# SDRAM.net
KiCad netlist of a schematic drawn in Altium Designer
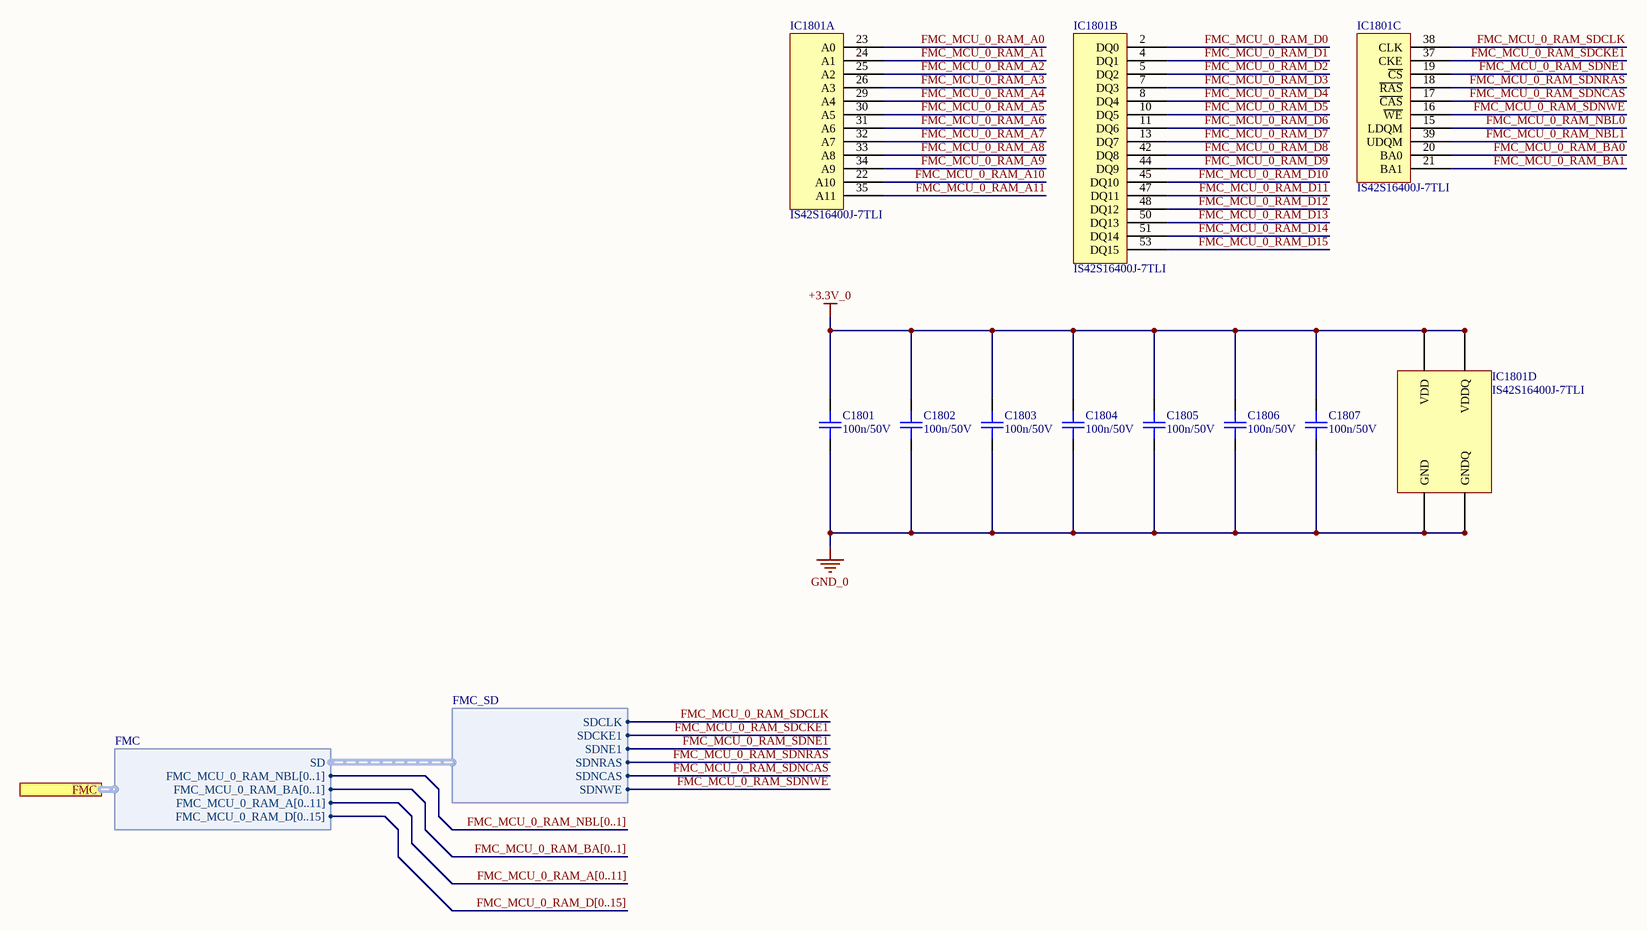
[diagram p0: SDRAM.SchDoc]

(export (version "E")
  (design (tool "Eeschema 10.0.6"))
  (components
    (comp (ref "C1801")
      (value "100n/50V")
      (footprint "CAPC1608X08N")
      (description "MLCC")
      (fields (field (name "PART NUMBER") "gen_C_ceramic_100n_50V_X7R_0603"))
      (libsource (lib "OE750") (part "C"))
    )
    (comp (ref "C1802")
      (value "100n/50V")
      (footprint "CAPC1608X08N")
      (description "MLCC")
      (fields (field (name "PART NUMBER") "gen_C_ceramic_100n_50V_X7R_0603"))
      (libsource (lib "OE750") (part "C"))
    )
    (comp (ref "C1803")
      (value "100n/50V")
      (footprint "CAPC1608X08N")
      (description "MLCC")
      (fields (field (name "PART NUMBER") "gen_C_ceramic_100n_50V_X7R_0603"))
      (libsource (lib "OE750") (part "C"))
    )
    (comp (ref "C1804")
      (value "100n/50V")
      (footprint "CAPC1608X08N")
      (description "MLCC")
      (fields (field (name "PART NUMBER") "gen_C_ceramic_100n_50V_X7R_0603"))
      (libsource (lib "OE750") (part "C"))
    )
    (comp (ref "C1805")
      (value "100n/50V")
      (footprint "CAPC1608X08N")
      (description "MLCC")
      (fields (field (name "PART NUMBER") "gen_C_ceramic_100n_50V_X7R_0603"))
      (libsource (lib "OE750") (part "C"))
    )
    (comp (ref "C1806")
      (value "100n/50V")
      (footprint "CAPC1608X08N")
      (description "MLCC")
      (fields (field (name "PART NUMBER") "gen_C_ceramic_100n_50V_X7R_0603"))
      (libsource (lib "OE750") (part "C"))
    )
    (comp (ref "C1807")
      (value "100n/50V")
      (footprint "CAPC1608X08N")
      (description "MLCC")
      (fields (field (name "PART NUMBER") "gen_C_ceramic_100n_50V_X7R_0603"))
      (libsource (lib "OE750") (part "C"))
    )
    (comp (ref "IC1801")
      (value "IS42S16400J-7TLI")
      (footprint "TSOP80P1180X120-54N")
      (description "SDRAM, 4M x 16 Bit")
      (fields (field (name "MANUFACTURER") "INTEGRATED SILICON SOLUTION (ISSI)"))
      (libsource (lib "OE750") (part "IS42S16400J-7TLI"))
    )
  )
  (nets
    (net (code "3") (name "+3.3V_0") (class "Default")
      (node (ref "C1801") (pin "1") (pinfunction "1_1") (pintype "passive"))
      (node (ref "C1802") (pin "1") (pinfunction "1_1") (pintype "passive"))
      (node (ref "C1803") (pin "1") (pinfunction "1_1") (pintype "passive"))
      (node (ref "C1804") (pin "1") (pinfunction "1_1") (pintype "passive"))
      (node (ref "C1805") (pin "1") (pinfunction "1_1") (pintype "passive"))
      (node (ref "C1806") (pin "1") (pinfunction "1_1") (pintype "passive"))
      (node (ref "C1807") (pin "1") (pinfunction "1_1") (pintype "passive"))
      (node (ref "IC1801") (pin "1") (pinfunction "VDD_1") (pintype "power_in"))
      (node (ref "IC1801") (pin "14") (pinfunction "VDD_14") (pintype "power_in"))
      (node (ref "IC1801") (pin "27") (pinfunction "VDD_27") (pintype "power_in"))
      (node (ref "IC1801") (pin "3") (pinfunction "VDDQ_3") (pintype "power_in"))
      (node (ref "IC1801") (pin "43") (pinfunction "VDDQ_43") (pintype "power_in"))
      (node (ref "IC1801") (pin "49") (pinfunction "VDDQ_49") (pintype "power_in"))
      (node (ref "IC1801") (pin "9") (pinfunction "VDDQ_9") (pintype "power_in"))
    )
    (net (code "4") (name "/FMC_MCU_0_RAM_A0") (class "Default")
      (node (ref "IC1801") (pin "23") (pinfunction "A0_23") (pintype "passive"))
    )
    (net (code "5") (name "/FMC_MCU_0_RAM_A1") (class "Default")
      (node (ref "IC1801") (pin "24") (pinfunction "A1_24") (pintype "passive"))
    )
    (net (code "6") (name "/FMC_MCU_0_RAM_A2") (class "Default")
      (node (ref "IC1801") (pin "25") (pinfunction "A2_25") (pintype "passive"))
    )
    (net (code "7") (name "/FMC_MCU_0_RAM_A3") (class "Default")
      (node (ref "IC1801") (pin "26") (pinfunction "A3_26") (pintype "passive"))
    )
    (net (code "8") (name "/FMC_MCU_0_RAM_A4") (class "Default")
      (node (ref "IC1801") (pin "29") (pinfunction "A4_29") (pintype "passive"))
    )
    (net (code "9") (name "/FMC_MCU_0_RAM_A5") (class "Default")
      (node (ref "IC1801") (pin "30") (pinfunction "A5_30") (pintype "passive"))
    )
    (net (code "10") (name "/FMC_MCU_0_RAM_A6") (class "Default")
      (node (ref "IC1801") (pin "31") (pinfunction "A6_31") (pintype "passive"))
    )
    (net (code "11") (name "/FMC_MCU_0_RAM_A7") (class "Default")
      (node (ref "IC1801") (pin "32") (pinfunction "A7_32") (pintype "passive"))
    )
    (net (code "12") (name "/FMC_MCU_0_RAM_A8") (class "Default")
      (node (ref "IC1801") (pin "33") (pinfunction "A8_33") (pintype "passive"))
    )
    (net (code "13") (name "/FMC_MCU_0_RAM_A9") (class "Default")
      (node (ref "IC1801") (pin "34") (pinfunction "A9_34") (pintype "passive"))
    )
    (net (code "14") (name "/FMC_MCU_0_RAM_A10") (class "Default")
      (node (ref "IC1801") (pin "22") (pinfunction "A10_22") (pintype "passive"))
    )
    (net (code "15") (name "/FMC_MCU_0_RAM_A11") (class "Default")
      (node (ref "IC1801") (pin "35") (pinfunction "A11_35") (pintype "passive"))
    )
    (net (code "17") (name "/FMC_MCU_0_RAM_BA0") (class "Default")
      (node (ref "IC1801") (pin "20") (pinfunction "BA0_20") (pintype "passive"))
    )
    (net (code "18") (name "/FMC_MCU_0_RAM_BA1") (class "Default")
      (node (ref "IC1801") (pin "21") (pinfunction "BA1_21") (pintype "passive"))
    )
    (net (code "20") (name "/FMC_MCU_0_RAM_D0") (class "Default")
      (node (ref "IC1801") (pin "2") (pinfunction "DQ0_2") (pintype "passive"))
    )
    (net (code "21") (name "/FMC_MCU_0_RAM_D1") (class "Default")
      (node (ref "IC1801") (pin "4") (pinfunction "DQ1_4") (pintype "passive"))
    )
    (net (code "22") (name "/FMC_MCU_0_RAM_D2") (class "Default")
      (node (ref "IC1801") (pin "5") (pinfunction "DQ2_5") (pintype "passive"))
    )
    (net (code "23") (name "/FMC_MCU_0_RAM_D3") (class "Default")
      (node (ref "IC1801") (pin "7") (pinfunction "DQ3_7") (pintype "passive"))
    )
    (net (code "24") (name "/FMC_MCU_0_RAM_D4") (class "Default")
      (node (ref "IC1801") (pin "8") (pinfunction "DQ4_8") (pintype "passive"))
    )
    (net (code "25") (name "/FMC_MCU_0_RAM_D5") (class "Default")
      (node (ref "IC1801") (pin "10") (pinfunction "DQ5_10") (pintype "passive"))
    )
    (net (code "26") (name "/FMC_MCU_0_RAM_D6") (class "Default")
      (node (ref "IC1801") (pin "11") (pinfunction "DQ6_11") (pintype "passive"))
    )
    (net (code "27") (name "/FMC_MCU_0_RAM_D7") (class "Default")
      (node (ref "IC1801") (pin "13") (pinfunction "DQ7_13") (pintype "passive"))
    )
    (net (code "28") (name "/FMC_MCU_0_RAM_D8") (class "Default")
      (node (ref "IC1801") (pin "42") (pinfunction "DQ8_42") (pintype "passive"))
    )
    (net (code "29") (name "/FMC_MCU_0_RAM_D9") (class "Default")
      (node (ref "IC1801") (pin "44") (pinfunction "DQ9_44") (pintype "passive"))
    )
    (net (code "30") (name "/FMC_MCU_0_RAM_D10") (class "Default")
      (node (ref "IC1801") (pin "45") (pinfunction "DQ10_45") (pintype "passive"))
    )
    (net (code "31") (name "/FMC_MCU_0_RAM_D11") (class "Default")
      (node (ref "IC1801") (pin "47") (pinfunction "DQ11_47") (pintype "passive"))
    )
    (net (code "32") (name "/FMC_MCU_0_RAM_D12") (class "Default")
      (node (ref "IC1801") (pin "48") (pinfunction "DQ12_48") (pintype "passive"))
    )
    (net (code "33") (name "/FMC_MCU_0_RAM_D13") (class "Default")
      (node (ref "IC1801") (pin "50") (pinfunction "DQ13_50") (pintype "passive"))
    )
    (net (code "34") (name "/FMC_MCU_0_RAM_D14") (class "Default")
      (node (ref "IC1801") (pin "51") (pinfunction "DQ14_51") (pintype "passive"))
    )
    (net (code "35") (name "/FMC_MCU_0_RAM_D15") (class "Default")
      (node (ref "IC1801") (pin "53") (pinfunction "DQ15_53") (pintype "passive"))
    )
    (net (code "36") (name "/FMC_MCU_0_RAM_NBL0") (class "Default")
      (node (ref "IC1801") (pin "15") (pinfunction "LDQM_15") (pintype "passive"))
    )
    (net (code "37") (name "/FMC_MCU_0_RAM_NBL1") (class "Default")
      (node (ref "IC1801") (pin "39") (pinfunction "UDQM_39") (pintype "passive"))
    )
    (net (code "39") (name "/FMC_MCU_0_RAM_SDCKE1") (class "Default")
      (node (ref "IC1801") (pin "37") (pinfunction "CKE_37") (pintype "passive"))
    )
    (net (code "40") (name "/FMC_MCU_0_RAM_SDCLK") (class "Default")
      (node (ref "IC1801") (pin "38") (pinfunction "CLK_38") (pintype "passive"))
    )
    (net (code "41") (name "/FMC_MCU_0_RAM_SDNCAS") (class "Default")
      (node (ref "IC1801") (pin "17") (pinfunction "~{CAS}_17") (pintype "passive"))
    )
    (net (code "42") (name "/FMC_MCU_0_RAM_SDNE1") (class "Default")
      (node (ref "IC1801") (pin "19") (pinfunction "~{CS}_19") (pintype "passive"))
    )
    (net (code "43") (name "/FMC_MCU_0_RAM_SDNRAS") (class "Default")
      (node (ref "IC1801") (pin "18") (pinfunction "~{RAS}_18") (pintype "passive"))
    )
    (net (code "44") (name "/FMC_MCU_0_RAM_SDNWE") (class "Default")
      (node (ref "IC1801") (pin "16") (pinfunction "~{WE}_16") (pintype "passive"))
    )
    (net (code "47") (name "GND_0") (class "Default")
      (node (ref "C1801") (pin "2") (pinfunction "2_2") (pintype "passive"))
      (node (ref "C1802") (pin "2") (pinfunction "2_2") (pintype "passive"))
      (node (ref "C1803") (pin "2") (pinfunction "2_2") (pintype "passive"))
      (node (ref "C1804") (pin "2") (pinfunction "2_2") (pintype "passive"))
      (node (ref "C1805") (pin "2") (pinfunction "2_2") (pintype "passive"))
      (node (ref "C1806") (pin "2") (pinfunction "2_2") (pintype "passive"))
      (node (ref "C1807") (pin "2") (pinfunction "2_2") (pintype "passive"))
      (node (ref "IC1801") (pin "12") (pinfunction "GNDQ_12") (pintype "power_in"))
      (node (ref "IC1801") (pin "28") (pinfunction "GND_28") (pintype "power_in"))
      (node (ref "IC1801") (pin "41") (pinfunction "GND_41") (pintype "power_in"))
      (node (ref "IC1801") (pin "46") (pinfunction "GNDQ_46") (pintype "power_in"))
      (node (ref "IC1801") (pin "52") (pinfunction "GNDQ_52") (pintype "power_in"))
      (node (ref "IC1801") (pin "54") (pinfunction "GND_54") (pintype "power_in"))
      (node (ref "IC1801") (pin "6") (pinfunction "GNDQ_6") (pintype "power_in"))
    )
  )
)
